# TestBench.net
KiCad netlist of a schematic drawn in EAGLE
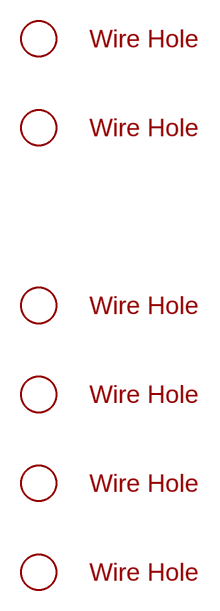
[diagram p0: schematic, sheet 1, part 1 of 2]
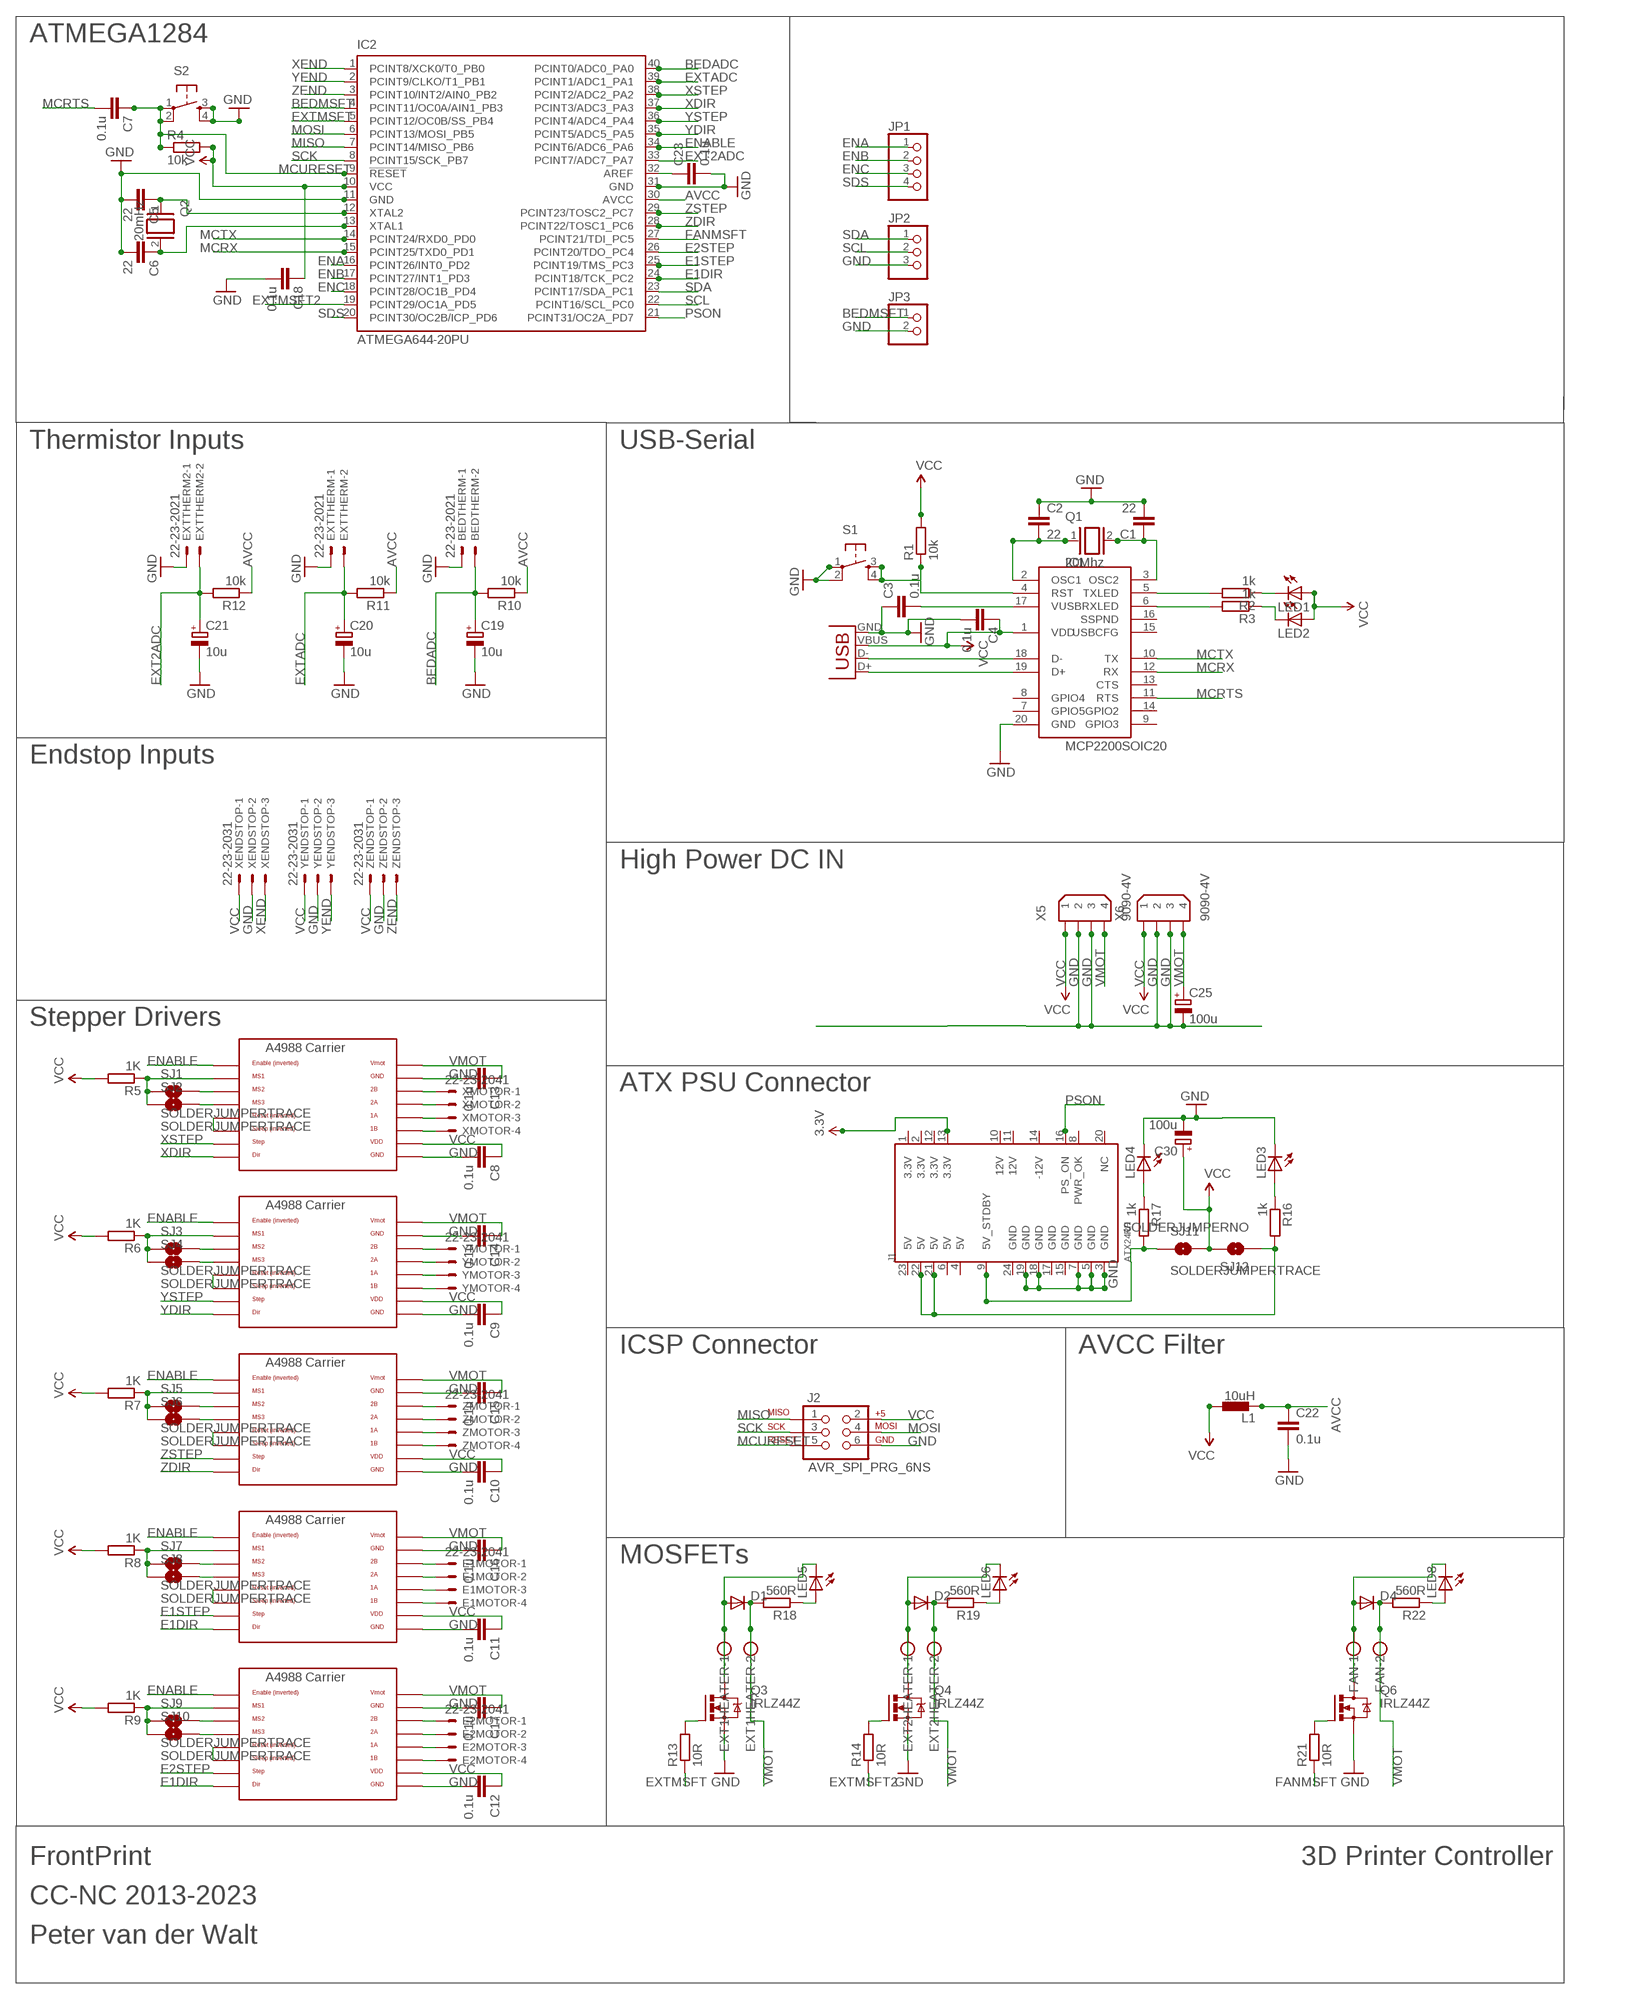
[diagram p1: schematic, sheet 1, part 2 of 2]

(export (version "E")
  (design (tool "Eeschema 10.0.6"))
  (components
    (comp (ref "BEDTHERM")
      (value "22-23-2021")
      (footprint "eagle-import:22-23-2021")
      (fields (field (name "MF") "MOLEX"))
      (libsource (lib "eagle-import") (part "22-23-2021"))
    )
    (comp (ref "C1")
      (value "22")
      (footprint "eagle-import:CAP-PTH-SMALL-KIT")
      (libsource (lib "eagle-import") (part "CAPKIT"))
    )
    (comp (ref "C2")
      (value "22")
      (footprint "eagle-import:CAP-PTH-SMALL-KIT")
      (libsource (lib "eagle-import") (part "CAPKIT"))
    )
    (comp (ref "C3")
      (value "0.1u")
      (footprint "eagle-import:CAP-PTH-SMALL-KIT")
      (libsource (lib "eagle-import") (part "CAPKIT"))
    )
    (comp (ref "C4")
      (value "0.1u")
      (footprint "eagle-import:CAP-PTH-SMALL-KIT")
      (libsource (lib "eagle-import") (part "CAPKIT"))
    )
    (comp (ref "C5")
      (value "22")
      (footprint "eagle-import:CAP-PTH-SMALL-KIT")
      (libsource (lib "eagle-import") (part "CAPKIT"))
    )
    (comp (ref "C6")
      (value "22")
      (footprint "eagle-import:CAP-PTH-SMALL-KIT")
      (libsource (lib "eagle-import") (part "CAPKIT"))
    )
    (comp (ref "C7")
      (value "0.1u")
      (footprint "eagle-import:CAP-PTH-SMALL-KIT")
      (libsource (lib "eagle-import") (part "CAPKIT"))
    )
    (comp (ref "C8")
      (value "0.1u")
      (footprint "eagle-import:CAP-PTH-SMALL-KIT")
      (libsource (lib "eagle-import") (part "CAPKIT"))
    )
    (comp (ref "C9")
      (value "0.1u")
      (footprint "eagle-import:CAP-PTH-SMALL-KIT")
      (libsource (lib "eagle-import") (part "CAPKIT"))
    )
    (comp (ref "C10")
      (value "0.1u")
      (footprint "eagle-import:CAP-PTH-SMALL-KIT")
      (libsource (lib "eagle-import") (part "CAPKIT"))
    )
    (comp (ref "C11")
      (value "0.1u")
      (footprint "eagle-import:CAP-PTH-SMALL-KIT")
      (libsource (lib "eagle-import") (part "CAPKIT"))
    )
    (comp (ref "C12")
      (value "0.1u")
      (footprint "eagle-import:CAP-PTH-SMALL-KIT")
      (libsource (lib "eagle-import") (part "CAPKIT"))
    )
    (comp (ref "C13")
      (value "0.1u")
      (footprint "eagle-import:CAP-PTH-SMALL-KIT")
      (libsource (lib "eagle-import") (part "CAPKIT"))
    )
    (comp (ref "C14")
      (value "0.1u")
      (footprint "eagle-import:CAP-PTH-SMALL-KIT")
      (libsource (lib "eagle-import") (part "CAPKIT"))
    )
    (comp (ref "C15")
      (value "0.1u")
      (footprint "eagle-import:CAP-PTH-SMALL-KIT")
      (libsource (lib "eagle-import") (part "CAPKIT"))
    )
    (comp (ref "C16")
      (value "0.1u")
      (footprint "eagle-import:CAP-PTH-SMALL-KIT")
      (libsource (lib "eagle-import") (part "CAPKIT"))
    )
    (comp (ref "C17")
      (value "0.1u")
      (footprint "eagle-import:CAP-PTH-SMALL-KIT")
      (libsource (lib "eagle-import") (part "CAPKIT"))
    )
    (comp (ref "C18")
      (value "0.1u")
      (footprint "eagle-import:CAP-PTH-SMALL-KIT")
      (libsource (lib "eagle-import") (part "CAPKIT"))
    )
    (comp (ref "C19")
      (value "10u")
      (footprint "eagle-import:E2,5-5")
      (libsource (lib "eagle-import") (part "CPOL-EUE2.5-5"))
    )
    (comp (ref "C20")
      (value "10u")
      (footprint "eagle-import:E2,5-5")
      (libsource (lib "eagle-import") (part "CPOL-EUE2.5-5"))
    )
    (comp (ref "C21")
      (value "10u")
      (footprint "eagle-import:E2,5-5")
      (libsource (lib "eagle-import") (part "CPOL-EUE2.5-5"))
    )
    (comp (ref "C22")
      (value "0.1u")
      (footprint "eagle-import:CAP-PTH-SMALL-KIT")
      (libsource (lib "eagle-import") (part "CAPKIT"))
    )
    (comp (ref "C23")
      (value "0.1u")
      (footprint "eagle-import:CAP-PTH-SMALL-KIT")
      (libsource (lib "eagle-import") (part "CAPKIT"))
    )
    (comp (ref "C25")
      (value "100u")
      (footprint "eagle-import:E5-8,5")
      (libsource (lib "eagle-import") (part "CPOL-EUE5-8.5"))
    )
    (comp (ref "C30")
      (value "100u")
      (footprint "eagle-import:E5-8,5")
      (libsource (lib "eagle-import") (part "CPOL-EUE5-8.5"))
    )
    (comp (ref "D1")
      (value "DIODE1N4148")
      (footprint "eagle-import:DIODE-1N4148")
      (libsource (lib "eagle-import") (part "DIODE1N4148"))
    )
    (comp (ref "D2")
      (value "DIODE1N4148")
      (footprint "eagle-import:DIODE-1N4148")
      (libsource (lib "eagle-import") (part "DIODE1N4148"))
    )
    (comp (ref "D4")
      (value "DIODE1N4148")
      (footprint "eagle-import:DIODE-1N4148")
      (libsource (lib "eagle-import") (part "DIODE1N4148"))
    )
    (comp (ref "E1MOTOR")
      (value "22-23-2041")
      (footprint "eagle-import:22-23-2041")
      (fields (field (name "MF") "MOLEX"))
      (libsource (lib "eagle-import") (part "22-23-2041"))
    )
    (comp (ref "E2MOTOR")
      (value "22-23-2041")
      (footprint "eagle-import:22-23-2041")
      (fields (field (name "MF") "MOLEX"))
      (libsource (lib "eagle-import") (part "22-23-2041"))
    )
    (comp (ref "EPOLOLU")
      (value "POLOLU_A4983CARRIER")
      (footprint "eagle-import:A4988BREAKOUT")
      (libsource (lib "eagle-import") (part "POLOLU_A4983CARRIER"))
    )
    (comp (ref "EPOLOLU2")
      (value "POLOLU_A4983CARRIER")
      (footprint "eagle-import:A4988BREAKOUT")
      (libsource (lib "eagle-import") (part "POLOLU_A4983CARRIER"))
    )
    (comp (ref "EXT1HEATER")
      (value "W237-102")
      (footprint "eagle-import:W237-102")
      (fields (field (name "MPN") "237-102"))
      (libsource (lib "eagle-import") (part "W237-102"))
    )
    (comp (ref "EXT2HEATER")
      (value "W237-102")
      (footprint "eagle-import:W237-102")
      (fields (field (name "MPN") "237-102"))
      (libsource (lib "eagle-import") (part "W237-102"))
    )
    (comp (ref "EXTTHERM")
      (value "22-23-2021")
      (footprint "eagle-import:22-23-2021")
      (fields (field (name "MF") "MOLEX"))
      (libsource (lib "eagle-import") (part "22-23-2021"))
    )
    (comp (ref "EXTTHERM2")
      (value "22-23-2021")
      (footprint "eagle-import:22-23-2021")
      (fields (field (name "MF") "MOLEX"))
      (libsource (lib "eagle-import") (part "22-23-2021"))
    )
    (comp (ref "FAN")
      (value "W237-102")
      (footprint "eagle-import:W237-102")
      (fields (field (name "MPN") "237-102"))
      (libsource (lib "eagle-import") (part "W237-102"))
    )
    (comp (ref "IC1")
      (value "MCP2200SOIC20")
      (footprint "eagle-import:SOIC20")
      (libsource (lib "eagle-import") (part "MCP2200SOIC20"))
    )
    (comp (ref "IC2")
      (value "ATMEGA644-20PU")
      (footprint "eagle-import:DIL40")
      (libsource (lib "eagle-import") (part "ATMEGA644-PU20"))
    )
    (comp (ref "J1")
      (value "ATX24RH")
      (footprint "eagle-import:ATX24_RIGHT_ANGLE")
      (libsource (lib "eagle-import") (part "ATX24RH"))
    )
    (comp (ref "J2")
      (value "AVR_SPI_PRG_6NS")
      (footprint "eagle-import:2X3-NS")
      (libsource (lib "eagle-import") (part "AVR_SPI_PRG_6NS"))
    )
    (comp (ref "JP1")
      (value "PINHD-1X4")
      (footprint "eagle-import:1X04")
      (libsource (lib "eagle-import") (part "PINHD-1X4"))
    )
    (comp (ref "JP2")
      (value "PINHD-1X3")
      (footprint "eagle-import:1X03")
      (libsource (lib "eagle-import") (part "PINHD-1X3"))
    )
    (comp (ref "JP3")
      (value "PINHD-1X2")
      (footprint "eagle-import:1X02")
      (libsource (lib "eagle-import") (part "PINHD-1X2"))
    )
    (comp (ref "L1")
      (value "10uH")
      (footprint "eagle-import:BL01RN1A")
      (libsource (lib "eagle-import") (part "BL01RN1A"))
    )
    (comp (ref "LED1")
      (value "LED3MM")
      (footprint "eagle-import:LED3MM")
      (libsource (lib "eagle-import") (part "LED3MM"))
    )
    (comp (ref "LED2")
      (value "LED3MM")
      (footprint "eagle-import:LED3MM")
      (libsource (lib "eagle-import") (part "LED3MM"))
    )
    (comp (ref "LED3")
      (value "LED3MM")
      (footprint "eagle-import:LED3MM")
      (libsource (lib "eagle-import") (part "LED3MM"))
    )
    (comp (ref "LED4")
      (value "LED3MM")
      (footprint "eagle-import:LED3MM")
      (libsource (lib "eagle-import") (part "LED3MM"))
    )
    (comp (ref "LED5")
      (value "LED3MM")
      (footprint "eagle-import:LED3MM")
      (libsource (lib "eagle-import") (part "LED3MM"))
    )
    (comp (ref "LED6")
      (value "LED3MM")
      (footprint "eagle-import:LED3MM")
      (libsource (lib "eagle-import") (part "LED3MM"))
    )
    (comp (ref "LED8")
      (value "LED3MM")
      (footprint "eagle-import:LED3MM")
      (libsource (lib "eagle-import") (part "LED3MM"))
    )
    (comp (ref "Q1")
      (value "20Mhz")
      (footprint "eagle-import:QS")
      (libsource (lib "eagle-import") (part "XTAL/S"))
    )
    (comp (ref "Q2")
      (value "20mHz")
      (footprint "eagle-import:QS")
      (libsource (lib "eagle-import") (part "XTAL/S"))
    )
    (comp (ref "Q3")
      (value "IRLZ44Z")
      (footprint "eagle-import:TO220BH")
      (libsource (lib "eagle-import") (part "IRLZ44Z"))
    )
    (comp (ref "Q4")
      (value "IRLZ44Z")
      (footprint "eagle-import:TO220BH")
      (libsource (lib "eagle-import") (part "IRLZ44Z"))
    )
    (comp (ref "Q6")
      (value "IRLZ44Z")
      (footprint "eagle-import:TO220BH")
      (libsource (lib "eagle-import") (part "IRLZ44Z"))
    )
    (comp (ref "R1")
      (value "10k")
      (footprint "eagle-import:0204_7")
      (libsource (lib "eagle-import") (part "R-EU_0204/7"))
    )
    (comp (ref "R2")
      (value "1k")
      (footprint "eagle-import:0204_7")
      (libsource (lib "eagle-import") (part "R-EU_0204/7"))
    )
    (comp (ref "R3")
      (value "1k")
      (footprint "eagle-import:0204_7")
      (libsource (lib "eagle-import") (part "R-EU_0204/7"))
    )
    (comp (ref "R4")
      (value "10k")
      (footprint "eagle-import:0204_7")
      (libsource (lib "eagle-import") (part "R-EU_0204/7"))
    )
    (comp (ref "R5")
      (value "1K")
      (footprint "eagle-import:0204_7")
      (libsource (lib "eagle-import") (part "R-EU_0204/7"))
    )
    (comp (ref "R6")
      (value "1K")
      (footprint "eagle-import:0204_7")
      (libsource (lib "eagle-import") (part "R-EU_0204/7"))
    )
    (comp (ref "R7")
      (value "1K")
      (footprint "eagle-import:0204_7")
      (libsource (lib "eagle-import") (part "R-EU_0204/7"))
    )
    (comp (ref "R8")
      (value "1K")
      (footprint "eagle-import:0204_7")
      (libsource (lib "eagle-import") (part "R-EU_0204/7"))
    )
    (comp (ref "R9")
      (value "1K")
      (footprint "eagle-import:0204_7")
      (libsource (lib "eagle-import") (part "R-EU_0204/7"))
    )
    (comp (ref "R10")
      (value "10k")
      (footprint "eagle-import:0204_7")
      (libsource (lib "eagle-import") (part "R-EU_0204/7"))
    )
    (comp (ref "R11")
      (value "10k")
      (footprint "eagle-import:0204_7")
      (libsource (lib "eagle-import") (part "R-EU_0204/7"))
    )
    (comp (ref "R12")
      (value "10k")
      (footprint "eagle-import:0204_7")
      (libsource (lib "eagle-import") (part "R-EU_0204/7"))
    )
    (comp (ref "R13")
      (value "10R")
      (footprint "eagle-import:0204_7")
      (libsource (lib "eagle-import") (part "R-EU_0204/7"))
    )
    (comp (ref "R14")
      (value "10R")
      (footprint "eagle-import:0204_7")
      (libsource (lib "eagle-import") (part "R-EU_0204/7"))
    )
    (comp (ref "R16")
      (value "1k")
      (footprint "eagle-import:0204_7")
      (libsource (lib "eagle-import") (part "R-EU_0204/7"))
    )
    (comp (ref "R17")
      (value "1k")
      (footprint "eagle-import:0204_7")
      (libsource (lib "eagle-import") (part "R-EU_0204/7"))
    )
    (comp (ref "R18")
      (value "560R")
      (footprint "eagle-import:0204_7")
      (libsource (lib "eagle-import") (part "R-EU_0204/7"))
    )
    (comp (ref "R19")
      (value "560R")
      (footprint "eagle-import:0204_7")
      (libsource (lib "eagle-import") (part "R-EU_0204/7"))
    )
    (comp (ref "R21")
      (value "10R")
      (footprint "eagle-import:0204_7")
      (libsource (lib "eagle-import") (part "R-EU_0204/7"))
    )
    (comp (ref "R22")
      (value "560R")
      (footprint "eagle-import:0204_7")
      (libsource (lib "eagle-import") (part "R-EU_0204/7"))
    )
    (comp (ref "S1")
      (value "TAC_SWITCHPTH")
      (footprint "eagle-import:TACTILE-PTH")
      (libsource (lib "eagle-import") (part "TAC_SWITCHPTH"))
    )
    (comp (ref "S2")
      (value "TAC_SWITCHPTH")
      (footprint "eagle-import:TACTILE-PTH")
      (libsource (lib "eagle-import") (part "TAC_SWITCHPTH"))
    )
    (comp (ref "SJ1")
      (value "SOLDERJUMPERTRACE")
      (footprint "eagle-import:SJ_2S-TRACE")
      (libsource (lib "eagle-import") (part "SOLDERJUMPERTRACE"))
    )
    (comp (ref "SJ2")
      (value "SOLDERJUMPERTRACE")
      (footprint "eagle-import:SJ_2S-TRACE")
      (libsource (lib "eagle-import") (part "SOLDERJUMPERTRACE"))
    )
    (comp (ref "SJ3")
      (value "SOLDERJUMPERTRACE")
      (footprint "eagle-import:SJ_2S-TRACE")
      (libsource (lib "eagle-import") (part "SOLDERJUMPERTRACE"))
    )
    (comp (ref "SJ4")
      (value "SOLDERJUMPERTRACE")
      (footprint "eagle-import:SJ_2S-TRACE")
      (libsource (lib "eagle-import") (part "SOLDERJUMPERTRACE"))
    )
    (comp (ref "SJ5")
      (value "SOLDERJUMPERTRACE")
      (footprint "eagle-import:SJ_2S-TRACE")
      (libsource (lib "eagle-import") (part "SOLDERJUMPERTRACE"))
    )
    (comp (ref "SJ6")
      (value "SOLDERJUMPERTRACE")
      (footprint "eagle-import:SJ_2S-TRACE")
      (libsource (lib "eagle-import") (part "SOLDERJUMPERTRACE"))
    )
    (comp (ref "SJ7")
      (value "SOLDERJUMPERTRACE")
      (footprint "eagle-import:SJ_2S-TRACE")
      (libsource (lib "eagle-import") (part "SOLDERJUMPERTRACE"))
    )
    (comp (ref "SJ8")
      (value "SOLDERJUMPERTRACE")
      (footprint "eagle-import:SJ_2S-TRACE")
      (libsource (lib "eagle-import") (part "SOLDERJUMPERTRACE"))
    )
    (comp (ref "SJ9")
      (value "SOLDERJUMPERTRACE")
      (footprint "eagle-import:SJ_2S-TRACE")
      (libsource (lib "eagle-import") (part "SOLDERJUMPERTRACE"))
    )
    (comp (ref "SJ10")
      (value "SOLDERJUMPERTRACE")
      (footprint "eagle-import:SJ_2S-TRACE")
      (libsource (lib "eagle-import") (part "SOLDERJUMPERTRACE"))
    )
    (comp (ref "SJ11")
      (value "SOLDERJUMPERTRACE")
      (footprint "eagle-import:SJ_2S-TRACE")
      (libsource (lib "eagle-import") (part "SOLDERJUMPERTRACE"))
    )
    (comp (ref "SJ12")
      (value "SOLDERJUMPERNO")
      (footprint "eagle-import:SJ_2S-NO")
      (libsource (lib "eagle-import") (part "SOLDERJUMPERNO"))
    )
    (comp (ref "U$1")
      (value "3MMHOLE")
      (footprint "eagle-import:3MMHOLE")
      (libsource (lib "eagle-import") (part "3MMHOLE"))
    )
    (comp (ref "U$3")
      (value "3MMHOLE")
      (footprint "eagle-import:3MMHOLE")
      (libsource (lib "eagle-import") (part "3MMHOLE"))
    )
    (comp (ref "U$5")
      (value "3MMHOLE")
      (footprint "eagle-import:3MMHOLE")
      (libsource (lib "eagle-import") (part "3MMHOLE"))
    )
    (comp (ref "U$6")
      (value "3MMHOLE")
      (footprint "eagle-import:3MMHOLE")
      (libsource (lib "eagle-import") (part "3MMHOLE"))
    )
    (comp (ref "U$7")
      (value "3MMHOLE")
      (footprint "eagle-import:3MMHOLE")
      (libsource (lib "eagle-import") (part "3MMHOLE"))
    )
    (comp (ref "U$8")
      (value "3MMHOLE")
      (footprint "eagle-import:3MMHOLE")
      (libsource (lib "eagle-import") (part "3MMHOLE"))
    )
    (comp (ref "X1")
      (value "USBPTH")
      (footprint "eagle-import:USB-B-PTH")
      (libsource (lib "eagle-import") (part "USBPTH"))
    )
    (comp (ref "X5")
      (value "9090-4V")
      (footprint "eagle-import:9090-4V")
      (libsource (lib "eagle-import") (part "9090-4V"))
    )
    (comp (ref "X6")
      (value "9090-4V")
      (footprint "eagle-import:9090-4V")
      (libsource (lib "eagle-import") (part "9090-4V"))
    )
    (comp (ref "XENDSTOP")
      (value "22-23-2031")
      (footprint "eagle-import:22-23-2031")
      (fields (field (name "MF") "MOLEX"))
      (libsource (lib "eagle-import") (part "22-23-2031"))
    )
    (comp (ref "XMOTOR")
      (value "22-23-2041")
      (footprint "eagle-import:22-23-2041")
      (fields (field (name "MF") "MOLEX"))
      (libsource (lib "eagle-import") (part "22-23-2041"))
    )
    (comp (ref "XPOLOLU")
      (value "POLOLU_A4983CARRIER")
      (footprint "eagle-import:A4988BREAKOUT")
      (libsource (lib "eagle-import") (part "POLOLU_A4983CARRIER"))
    )
    (comp (ref "YENDSTOP")
      (value "22-23-2031")
      (footprint "eagle-import:22-23-2031")
      (fields (field (name "MF") "MOLEX"))
      (libsource (lib "eagle-import") (part "22-23-2031"))
    )
    (comp (ref "YMOTOR")
      (value "22-23-2041")
      (footprint "eagle-import:22-23-2041")
      (fields (field (name "MF") "MOLEX"))
      (libsource (lib "eagle-import") (part "22-23-2041"))
    )
    (comp (ref "YPOLOLU")
      (value "POLOLU_A4983CARRIER")
      (footprint "eagle-import:A4988BREAKOUT")
      (libsource (lib "eagle-import") (part "POLOLU_A4983CARRIER"))
    )
    (comp (ref "ZENDSTOP")
      (value "22-23-2031")
      (footprint "eagle-import:22-23-2031")
      (fields (field (name "MF") "MOLEX"))
      (libsource (lib "eagle-import") (part "22-23-2031"))
    )
    (comp (ref "ZMOTOR")
      (value "22-23-2041")
      (footprint "eagle-import:22-23-2041")
      (fields (field (name "MF") "MOLEX"))
      (libsource (lib "eagle-import") (part "22-23-2041"))
    )
    (comp (ref "ZPOLOLU")
      (value "POLOLU_A4983CARRIER")
      (footprint "eagle-import:A4988BREAKOUT")
      (libsource (lib "eagle-import") (part "POLOLU_A4983CARRIER"))
    )
  )
  (nets
    (net (code "1") (name "/AVCC") (class "Default")
      (node (ref "C22") (pin "1") (pinfunction "1_1") (pintype "passive"))
      (node (ref "IC2") (pin "30") (pinfunction "AVCC_30") (pintype "power_in"))
      (node (ref "L1") (pin "1") (pinfunction "1_1") (pintype "passive"))
      (node (ref "R10") (pin "1") (pinfunction "1_1") (pintype "passive"))
      (node (ref "R11") (pin "1") (pinfunction "1_1") (pintype "passive"))
      (node (ref "R12") (pin "1") (pinfunction "1_1") (pintype "passive"))
    )
    (net (code "2") (name "/BEDADC") (class "Default")
      (node (ref "BEDTHERM") (pin "2") (pinfunction "S_2") (pintype "passive"))
      (node (ref "C19") (pin "+") (pinfunction "+_+") (pintype "passive"))
      (node (ref "IC2") (pin "40") (pinfunction "PCINT0/ADC0_PA0_40") (pintype "bidirectional"))
      (node (ref "R10") (pin "2") (pinfunction "2_2") (pintype "passive"))
    )
    (net (code "3") (name "/BEDMSFT") (class "Default")
      (node (ref "IC2") (pin "4") (pinfunction "PCINT11/OC0A/AIN1_PB3_4") (pintype "bidirectional"))
      (node (ref "JP3") (pin "1") (pinfunction "1_1") (pintype "passive"))
    )
    (net (code "4") (name "/E1DIR") (class "Default")
      (node (ref "EPOLOLU") (pin "DIR") (pinfunction "DIR_DIR") (pintype "input"))
      (node (ref "EPOLOLU2") (pin "DIR") (pinfunction "DIR_DIR") (pintype "input"))
      (node (ref "IC2") (pin "24") (pinfunction "PCINT18/TCK_PC2_24") (pintype "bidirectional"))
    )
    (net (code "5") (name "/E1STEP") (class "Default")
      (node (ref "EPOLOLU") (pin "STEP") (pinfunction "STEP_STEP") (pintype "input"))
      (node (ref "IC2") (pin "25") (pinfunction "PCINT19/TMS_PC3_25") (pintype "bidirectional"))
    )
    (net (code "6") (name "/E2STEP") (class "Default")
      (node (ref "EPOLOLU2") (pin "STEP") (pinfunction "STEP_STEP") (pintype "input"))
      (node (ref "IC2") (pin "26") (pinfunction "PCINT20/TDO_PC4_26") (pintype "bidirectional"))
    )
    (net (code "7") (name "/ENA") (class "Default")
      (node (ref "IC2") (pin "16") (pinfunction "PCINT26/INT0_PD2_16") (pintype "bidirectional"))
      (node (ref "JP1") (pin "1") (pinfunction "1_1") (pintype "passive"))
    )
    (net (code "8") (name "/ENABLE") (class "Default")
      (node (ref "EPOLOLU") (pin "EN") (pinfunction "EN_EN") (pintype "input"))
      (node (ref "EPOLOLU2") (pin "EN") (pinfunction "EN_EN") (pintype "input"))
      (node (ref "IC2") (pin "34") (pinfunction "PCINT6/ADC6_PA6_34") (pintype "bidirectional"))
      (node (ref "XPOLOLU") (pin "EN") (pinfunction "EN_EN") (pintype "input"))
      (node (ref "YPOLOLU") (pin "EN") (pinfunction "EN_EN") (pintype "input"))
      (node (ref "ZPOLOLU") (pin "EN") (pinfunction "EN_EN") (pintype "input"))
    )
    (net (code "9") (name "/ENB") (class "Default")
      (node (ref "IC2") (pin "17") (pinfunction "PCINT27/INT1_PD3_17") (pintype "bidirectional"))
      (node (ref "JP1") (pin "2") (pinfunction "2_2") (pintype "passive"))
    )
    (net (code "10") (name "/ENC") (class "Default")
      (node (ref "IC2") (pin "18") (pinfunction "PCINT28/OC1B_PD4_18") (pintype "bidirectional"))
      (node (ref "JP1") (pin "3") (pinfunction "3_3") (pintype "passive"))
    )
    (net (code "11") (name "/EXT2ADC") (class "Default")
      (node (ref "C21") (pin "+") (pinfunction "+_+") (pintype "passive"))
      (node (ref "EXTTHERM2") (pin "2") (pinfunction "S_2") (pintype "passive"))
      (node (ref "IC2") (pin "33") (pinfunction "PCINT7/ADC7_PA7_33") (pintype "bidirectional"))
      (node (ref "R12") (pin "2") (pinfunction "2_2") (pintype "passive"))
    )
    (net (code "12") (name "/EXTADC") (class "Default")
      (node (ref "C20") (pin "+") (pinfunction "+_+") (pintype "passive"))
      (node (ref "EXTTHERM") (pin "2") (pinfunction "S_2") (pintype "passive"))
      (node (ref "IC2") (pin "39") (pinfunction "PCINT1/ADC1_PA1_39") (pintype "bidirectional"))
      (node (ref "R11") (pin "2") (pinfunction "2_2") (pintype "passive"))
    )
    (net (code "13") (name "/EXTMSFT") (class "Default")
      (node (ref "IC2") (pin "5") (pinfunction "PCINT12/OC0B/SS_PB4_5") (pintype "bidirectional"))
      (node (ref "R13") (pin "1") (pinfunction "1_1") (pintype "passive"))
    )
    (net (code "14") (name "/EXTMSFT2") (class "Default")
      (node (ref "IC2") (pin "19") (pinfunction "PCINT29/OC1A_PD5_19") (pintype "bidirectional"))
      (node (ref "R14") (pin "1") (pinfunction "1_1") (pintype "passive"))
    )
    (net (code "15") (name "/FANMSFT") (class "Default")
      (node (ref "IC2") (pin "27") (pinfunction "PCINT21/TDI_PC5_27") (pintype "bidirectional"))
      (node (ref "R21") (pin "1") (pinfunction "1_1") (pintype "passive"))
    )
    (net (code "16") (name "/MCRTS") (class "Default")
      (node (ref "C7") (pin "2") (pinfunction "2_2") (pintype "passive"))
      (node (ref "IC1") (pin "11") (pinfunction "RTS_11") (pintype "bidirectional"))
    )
    (net (code "17") (name "/MCRX") (class "Default")
      (node (ref "IC1") (pin "12") (pinfunction "RX_12") (pintype "bidirectional"))
      (node (ref "IC2") (pin "15") (pinfunction "PCINT25/TXD0_PD1_15") (pintype "bidirectional"))
    )
    (net (code "18") (name "/MCTX") (class "Default")
      (node (ref "IC1") (pin "10") (pinfunction "TX_10") (pintype "bidirectional"))
      (node (ref "IC2") (pin "14") (pinfunction "PCINT24/RXD0_PD0_14") (pintype "bidirectional"))
    )
    (net (code "19") (name "/MCURESET") (class "Default")
      (node (ref "C7") (pin "1") (pinfunction "1_1") (pintype "passive"))
      (node (ref "IC2") (pin "9") (pinfunction "~{RESET}_9") (pintype "input"))
      (node (ref "J2") (pin "5") (pinfunction "5_5") (pintype "passive"))
      (node (ref "R4") (pin "1") (pinfunction "1_1") (pintype "passive"))
      (node (ref "S2") (pin "1") (pinfunction "1_1") (pintype "passive"))
      (node (ref "S2") (pin "2") (pinfunction "2_2") (pintype "passive"))
    )
    (net (code "20") (name "/MISO") (class "Default")
      (node (ref "IC2") (pin "7") (pinfunction "PCINT14/MISO_PB6_7") (pintype "bidirectional"))
      (node (ref "J2") (pin "1") (pinfunction "1_1") (pintype "passive"))
    )
    (net (code "21") (name "/MOSI") (class "Default")
      (node (ref "IC2") (pin "6") (pinfunction "PCINT13/MOSI_PB5_6") (pintype "bidirectional"))
      (node (ref "J2") (pin "4") (pinfunction "4_4") (pintype "passive"))
    )
    (net (code "22") (name "/PSON") (class "Default")
      (node (ref "IC2") (pin "21") (pinfunction "PCINT31/OC2A_PD7_21") (pintype "bidirectional"))
      (node (ref "J1") (pin "16") (pinfunction "PS_ON_16") (pintype "bidirectional"))
    )
    (net (code "23") (name "/SCK") (class "Default")
      (node (ref "IC2") (pin "8") (pinfunction "PCINT15/SCK_PB7_8") (pintype "bidirectional"))
      (node (ref "J2") (pin "3") (pinfunction "3_3") (pintype "passive"))
    )
    (net (code "24") (name "/SCL") (class "Default")
      (node (ref "IC2") (pin "22") (pinfunction "PCINT16/SCL_PC0_22") (pintype "bidirectional"))
      (node (ref "JP2") (pin "2") (pinfunction "2_2") (pintype "passive"))
    )
    (net (code "25") (name "/SDA") (class "Default")
      (node (ref "IC2") (pin "23") (pinfunction "PCINT17/SDA_PC1_23") (pintype "bidirectional"))
      (node (ref "JP2") (pin "1") (pinfunction "1_1") (pintype "passive"))
    )
    (net (code "26") (name "/SDS") (class "Default")
      (node (ref "IC2") (pin "20") (pinfunction "PCINT30/OC2B/ICP_PD6_20") (pintype "bidirectional"))
      (node (ref "JP1") (pin "4") (pinfunction "4_4") (pintype "passive"))
    )
    (net (code "27") (name "/VMOT") (class "Default")
      (node (ref "C13") (pin "1") (pinfunction "1_1") (pintype "passive"))
      (node (ref "C14") (pin "1") (pinfunction "1_1") (pintype "passive"))
      (node (ref "C15") (pin "1") (pinfunction "1_1") (pintype "passive"))
      (node (ref "C16") (pin "1") (pinfunction "1_1") (pintype "passive"))
      (node (ref "C17") (pin "1") (pinfunction "1_1") (pintype "passive"))
      (node (ref "C25") (pin "+") (pinfunction "+_+") (pintype "passive"))
      (node (ref "D1") (pin "C") (pinfunction "C_C") (pintype "passive"))
      (node (ref "D2") (pin "C") (pinfunction "C_C") (pintype "passive"))
      (node (ref "D4") (pin "C") (pinfunction "C_C") (pintype "passive"))
      (node (ref "EPOLOLU") (pin "VMOT") (pinfunction "VMOT_VMOT") (pintype "power_in"))
      (node (ref "EPOLOLU2") (pin "VMOT") (pinfunction "VMOT_VMOT") (pintype "power_in"))
      (node (ref "EXT1HEATER") (pin "2") (pinfunction "KL_2") (pintype "passive"))
      (node (ref "EXT2HEATER") (pin "2") (pinfunction "KL_2") (pintype "passive"))
      (node (ref "FAN") (pin "2") (pinfunction "KL_2") (pintype "passive"))
      (node (ref "R18") (pin "2") (pinfunction "2_2") (pintype "passive"))
      (node (ref "R19") (pin "2") (pinfunction "2_2") (pintype "passive"))
      (node (ref "R22") (pin "2") (pinfunction "2_2") (pintype "passive"))
      (node (ref "X5") (pin "4") (pinfunction "4_4") (pintype "passive"))
      (node (ref "X6") (pin "4") (pinfunction "4_4") (pintype "passive"))
      (node (ref "XPOLOLU") (pin "VMOT") (pinfunction "VMOT_VMOT") (pintype "power_in"))
      (node (ref "YPOLOLU") (pin "VMOT") (pinfunction "VMOT_VMOT") (pintype "power_in"))
      (node (ref "ZPOLOLU") (pin "VMOT") (pinfunction "VMOT_VMOT") (pintype "power_in"))
    )
    (net (code "28") (name "/XDIR") (class "Default")
      (node (ref "IC2") (pin "37") (pinfunction "PCINT3/ADC3_PA3_37") (pintype "bidirectional"))
      (node (ref "XPOLOLU") (pin "DIR") (pinfunction "DIR_DIR") (pintype "input"))
    )
    (net (code "29") (name "/XEND") (class "Default")
      (node (ref "IC2") (pin "1") (pinfunction "PCINT8/XCK0/T0_PB0_1") (pintype "bidirectional"))
      (node (ref "XENDSTOP") (pin "3") (pinfunction "S_3") (pintype "passive"))
    )
    (net (code "30") (name "/XSTEP") (class "Default")
      (node (ref "IC2") (pin "38") (pinfunction "PCINT2/ADC2_PA2_38") (pintype "bidirectional"))
      (node (ref "XPOLOLU") (pin "STEP") (pinfunction "STEP_STEP") (pintype "input"))
    )
    (net (code "31") (name "/YDIR") (class "Default")
      (node (ref "IC2") (pin "35") (pinfunction "PCINT5/ADC5_PA5_35") (pintype "bidirectional"))
      (node (ref "YPOLOLU") (pin "DIR") (pinfunction "DIR_DIR") (pintype "input"))
    )
    (net (code "32") (name "/YEND") (class "Default")
      (node (ref "IC2") (pin "2") (pinfunction "PCINT9/CLKO/T1_PB1_2") (pintype "bidirectional"))
      (node (ref "YENDSTOP") (pin "3") (pinfunction "S_3") (pintype "passive"))
    )
    (net (code "33") (name "/YSTEP") (class "Default")
      (node (ref "IC2") (pin "36") (pinfunction "PCINT4/ADC4_PA4_36") (pintype "bidirectional"))
      (node (ref "YPOLOLU") (pin "STEP") (pinfunction "STEP_STEP") (pintype "input"))
    )
    (net (code "34") (name "/ZDIR") (class "Default")
      (node (ref "IC2") (pin "28") (pinfunction "PCINT22/TOSC1_PC6_28") (pintype "bidirectional"))
      (node (ref "ZPOLOLU") (pin "DIR") (pinfunction "DIR_DIR") (pintype "input"))
    )
    (net (code "35") (name "/ZEND") (class "Default")
      (node (ref "IC2") (pin "3") (pinfunction "PCINT10/INT2/AIN0_PB2_3") (pintype "bidirectional"))
      (node (ref "ZENDSTOP") (pin "3") (pinfunction "S_3") (pintype "passive"))
    )
    (net (code "36") (name "/ZSTEP") (class "Default")
      (node (ref "IC2") (pin "29") (pinfunction "PCINT23/TOSC2_PC7_29") (pintype "bidirectional"))
      (node (ref "ZPOLOLU") (pin "STEP") (pinfunction "STEP_STEP") (pintype "input"))
    )
    (net (code "37") (name "3.3V") (class "Default")
      (node (ref "J1") (pin "13") (pinfunction "3.3V_13") (pintype "bidirectional"))
    )
    (net (code "38") (name "GND") (class "Default")
      (node (ref "BEDTHERM") (pin "1") (pinfunction "S_1") (pintype "passive"))
      (node (ref "C1") (pin "2") (pinfunction "2_2") (pintype "passive"))
      (node (ref "C10") (pin "2") (pinfunction "2_2") (pintype "passive"))
      (node (ref "C11") (pin "2") (pinfunction "2_2") (pintype "passive"))
      (node (ref "C12") (pin "2") (pinfunction "2_2") (pintype "passive"))
      (node (ref "C13") (pin "2") (pinfunction "2_2") (pintype "passive"))
      (node (ref "C14") (pin "2") (pinfunction "2_2") (pintype "passive"))
      (node (ref "C15") (pin "2") (pinfunction "2_2") (pintype "passive"))
      (node (ref "C16") (pin "2") (pinfunction "2_2") (pintype "passive"))
      (node (ref "C17") (pin "2") (pinfunction "2_2") (pintype "passive"))
      (node (ref "C18") (pin "2") (pinfunction "2_2") (pintype "passive"))
      (node (ref "C19") (pin "-") (pinfunction "-_-") (pintype "passive"))
      (node (ref "C2") (pin "1") (pinfunction "1_1") (pintype "passive"))
      (node (ref "C20") (pin "-") (pinfunction "-_-") (pintype "passive"))
      (node (ref "C21") (pin "-") (pinfunction "-_-") (pintype "passive"))
      (node (ref "C22") (pin "2") (pinfunction "2_2") (pintype "passive"))
      (node (ref "C23") (pin "2") (pinfunction "2_2") (pintype "passive"))
      (node (ref "C25") (pin "-") (pinfunction "-_-") (pintype "passive"))
      (node (ref "C3") (pin "1") (pinfunction "1_1") (pintype "passive"))
      (node (ref "C30") (pin "-") (pinfunction "-_-") (pintype "passive"))
      (node (ref "C4") (pin "2") (pinfunction "2_2") (pintype "passive"))
      (node (ref "C5") (pin "2") (pinfunction "2_2") (pintype "passive"))
      (node (ref "C6") (pin "2") (pinfunction "2_2") (pintype "passive"))
      (node (ref "C8") (pin "2") (pinfunction "2_2") (pintype "passive"))
      (node (ref "C9") (pin "2") (pinfunction "2_2") (pintype "passive"))
      (node (ref "EPOLOLU") (pin "GND") (pinfunction "GND_GND") (pintype "power_in"))
      (node (ref "EPOLOLU") (pin "GND@0") (pinfunction "GND_GND@0") (pintype "power_in"))
      (node (ref "EPOLOLU2") (pin "GND") (pinfunction "GND_GND") (pintype "power_in"))
      (node (ref "EPOLOLU2") (pin "GND@0") (pinfunction "GND_GND@0") (pintype "power_in"))
      (node (ref "EXTTHERM") (pin "1") (pinfunction "S_1") (pintype "passive"))
      (node (ref "EXTTHERM2") (pin "1") (pinfunction "S_1") (pintype "passive"))
      (node (ref "IC1") (pin "20") (pinfunction "GND_20") (pintype "bidirectional"))
      (node (ref "IC2") (pin "11") (pinfunction "GND_11") (pintype "power_in"))
      (node (ref "IC2") (pin "31") (pinfunction "GND_31") (pintype "power_in"))
      (node (ref "J1") (pin "18") (pinfunction "GND_18") (pintype "bidirectional"))
      (node (ref "J1") (pin "19") (pinfunction "GND_19") (pintype "bidirectional"))
      (node (ref "J1") (pin "3") (pinfunction "GND_3") (pintype "bidirectional"))
      (node (ref "J1") (pin "5") (pinfunction "GND_5") (pintype "bidirectional"))
      (node (ref "J1") (pin "7") (pinfunction "GND_7") (pintype "bidirectional"))
      (node (ref "J2") (pin "6") (pinfunction "6_6") (pintype "passive"))
      (node (ref "JP2") (pin "3") (pinfunction "3_3") (pintype "passive"))
      (node (ref "JP3") (pin "2") (pinfunction "2_2") (pintype "passive"))
      (node (ref "LED3") (pin "K") (pinfunction "C_K") (pintype "passive"))
      (node (ref "LED4") (pin "K") (pinfunction "C_K") (pintype "passive"))
      (node (ref "Q3") (pin "S") (pinfunction "S_S") (pintype "passive"))
      (node (ref "Q4") (pin "S") (pinfunction "S_S") (pintype "passive"))
      (node (ref "Q6") (pin "S") (pinfunction "S_S") (pintype "passive"))
      (node (ref "S1") (pin "1") (pinfunction "1_1") (pintype "passive"))
      (node (ref "S1") (pin "2") (pinfunction "2_2") (pintype "passive"))
      (node (ref "S2") (pin "3") (pinfunction "3_3") (pintype "passive"))
      (node (ref "S2") (pin "4") (pinfunction "4_4") (pintype "passive"))
      (node (ref "X1") (pin "GND") (pinfunction "GND_GND") (pintype "bidirectional"))
      (node (ref "X5") (pin "2") (pinfunction "2_2") (pintype "passive"))
      (node (ref "X5") (pin "3") (pinfunction "3_3") (pintype "passive"))
      (node (ref "X6") (pin "2") (pinfunction "2_2") (pintype "passive"))
      (node (ref "X6") (pin "3") (pinfunction "3_3") (pintype "passive"))
      (node (ref "XENDSTOP") (pin "2") (pinfunction "S_2") (pintype "passive"))
      (node (ref "XPOLOLU") (pin "GND") (pinfunction "GND_GND") (pintype "power_in"))
      (node (ref "XPOLOLU") (pin "GND@0") (pinfunction "GND_GND@0") (pintype "power_in"))
      (node (ref "YENDSTOP") (pin "2") (pinfunction "S_2") (pintype "passive"))
      (node (ref "YPOLOLU") (pin "GND") (pinfunction "GND_GND") (pintype "power_in"))
      (node (ref "YPOLOLU") (pin "GND@0") (pinfunction "GND_GND@0") (pintype "power_in"))
      (node (ref "ZENDSTOP") (pin "2") (pinfunction "S_2") (pintype "passive"))
      (node (ref "ZPOLOLU") (pin "GND") (pinfunction "GND_GND") (pintype "power_in"))
      (node (ref "ZPOLOLU") (pin "GND@0") (pinfunction "GND_GND@0") (pintype "power_in"))
    )
    (net (code "39") (name "Net-(E1MOTORA-S)") (class "Default")
      (node (ref "E1MOTOR") (pin "1") (pinfunction "S_1") (pintype "passive"))
      (node (ref "EPOLOLU") (pin "2B") (pinfunction "2B_2B") (pintype "output"))
    )
    (net (code "40") (name "Net-(E1MOTORB-S)") (class "Default")
      (node (ref "E1MOTOR") (pin "2") (pinfunction "S_2") (pintype "passive"))
      (node (ref "EPOLOLU") (pin "2A") (pinfunction "2A_2A") (pintype "output"))
    )
    (net (code "41") (name "Net-(E1MOTORC-S)") (class "Default")
      (node (ref "E1MOTOR") (pin "3") (pinfunction "S_3") (pintype "passive"))
      (node (ref "EPOLOLU") (pin "1A") (pinfunction "1A_1A") (pintype "output"))
    )
    (net (code "42") (name "Net-(E1MOTORD-S)") (class "Default")
      (node (ref "E1MOTOR") (pin "4") (pinfunction "S_4") (pintype "passive"))
      (node (ref "EPOLOLU") (pin "1B") (pinfunction "1B_1B") (pintype "output"))
    )
    (net (code "43") (name "Net-(E2MOTORA-S)") (class "Default")
      (node (ref "E2MOTOR") (pin "1") (pinfunction "S_1") (pintype "passive"))
      (node (ref "EPOLOLU2") (pin "2B") (pinfunction "2B_2B") (pintype "output"))
    )
    (net (code "44") (name "Net-(E2MOTORB-S)") (class "Default")
      (node (ref "E2MOTOR") (pin "2") (pinfunction "S_2") (pintype "passive"))
      (node (ref "EPOLOLU2") (pin "2A") (pinfunction "2A_2A") (pintype "output"))
    )
    (net (code "45") (name "Net-(E2MOTORC-S)") (class "Default")
      (node (ref "E2MOTOR") (pin "3") (pinfunction "S_3") (pintype "passive"))
      (node (ref "EPOLOLU2") (pin "1A") (pinfunction "1A_1A") (pintype "output"))
    )
    (net (code "46") (name "Net-(E2MOTORD-S)") (class "Default")
      (node (ref "E2MOTOR") (pin "4") (pinfunction "S_4") (pintype "passive"))
      (node (ref "EPOLOLU2") (pin "1B") (pinfunction "1B_1B") (pintype "output"))
    )
    (net (code "47") (name "Net-(EPOLOLU-PadMS1)") (class "Default")
      (node (ref "EPOLOLU") (pin "MS1") (pinfunction "MS1_MS1") (pintype "input"))
      (node (ref "R8") (pin "1") (pinfunction "1_1") (pintype "passive"))
      (node (ref "SJ7") (pin "1") (pinfunction "1_1") (pintype "passive"))
      (node (ref "SJ8") (pin "1") (pinfunction "1_1") (pintype "passive"))
    )
    (net (code "48") (name "Net-(EPOLOLU-PadMS2)") (class "Default")
      (node (ref "EPOLOLU") (pin "MS2") (pinfunction "MS2_MS2") (pintype "input"))
      (node (ref "SJ7") (pin "2") (pinfunction "2_2") (pintype "passive"))
    )
    (net (code "49") (name "Net-(EPOLOLU-PadMS3)") (class "Default")
      (node (ref "EPOLOLU") (pin "MS3") (pinfunction "MS3_MS3") (pintype "input"))
      (node (ref "SJ8") (pin "2") (pinfunction "2_2") (pintype "passive"))
    )
    (net (code "50") (name "Net-(EPOLOLU-SLEEP)") (class "Default")
      (node (ref "EPOLOLU") (pin "RST") (pinfunction "RST_RST") (pintype "input"))
      (node (ref "EPOLOLU") (pin "SLP") (pinfunction "SLEEP_SLP") (pintype "input"))
    )
    (net (code "51") (name "Net-(EPOLOLU2-PadMS1)") (class "Default")
      (node (ref "EPOLOLU2") (pin "MS1") (pinfunction "MS1_MS1") (pintype "input"))
      (node (ref "R9") (pin "1") (pinfunction "1_1") (pintype "passive"))
      (node (ref "SJ10") (pin "1") (pinfunction "1_1") (pintype "passive"))
      (node (ref "SJ9") (pin "1") (pinfunction "1_1") (pintype "passive"))
    )
    (net (code "52") (name "Net-(EPOLOLU2-PadMS2)") (class "Default")
      (node (ref "EPOLOLU2") (pin "MS2") (pinfunction "MS2_MS2") (pintype "input"))
      (node (ref "SJ9") (pin "2") (pinfunction "2_2") (pintype "passive"))
    )
    (net (code "53") (name "Net-(EPOLOLU2-PadMS3)") (class "Default")
      (node (ref "EPOLOLU2") (pin "MS3") (pinfunction "MS3_MS3") (pintype "input"))
      (node (ref "SJ10") (pin "2") (pinfunction "2_2") (pintype "passive"))
    )
    (net (code "54") (name "Net-(EPOLOLU2-SLEEP)") (class "Default")
      (node (ref "EPOLOLU2") (pin "RST") (pinfunction "RST_RST") (pintype "input"))
      (node (ref "EPOLOLU2") (pin "SLP") (pinfunction "SLEEP_SLP") (pintype "input"))
    )
    (net (code "55") (name "Net-(EXT1HEATERA-KL)") (class "Default")
      (node (ref "D1") (pin "A") (pinfunction "A_A") (pintype "passive"))
      (node (ref "EXT1HEATER") (pin "1") (pinfunction "KL_1") (pintype "passive"))
      (node (ref "LED5") (pin "K") (pinfunction "C_K") (pintype "passive"))
      (node (ref "Q3") (pin "D") (pinfunction "D_D") (pintype "passive"))
    )
    (net (code "56") (name "Net-(EXT2HEATERA-KL)") (class "Default")
      (node (ref "D2") (pin "A") (pinfunction "A_A") (pintype "passive"))
      (node (ref "EXT2HEATER") (pin "1") (pinfunction "KL_1") (pintype "passive"))
      (node (ref "LED6") (pin "K") (pinfunction "C_K") (pintype "passive"))
      (node (ref "Q4") (pin "D") (pinfunction "D_D") (pintype "passive"))
    )
    (net (code "57") (name "Net-(FANA-KL)") (class "Default")
      (node (ref "D4") (pin "A") (pinfunction "A_A") (pintype "passive"))
      (node (ref "FAN") (pin "1") (pinfunction "KL_1") (pintype "passive"))
      (node (ref "LED8") (pin "K") (pinfunction "C_K") (pintype "passive"))
      (node (ref "Q6") (pin "D") (pinfunction "D_D") (pintype "passive"))
    )
    (net (code "58") (name "Net-(IC1-D+)") (class "Default")
      (node (ref "IC1") (pin "19") (pinfunction "D+_19") (pintype "bidirectional"))
      (node (ref "X1") (pin "D+") (pinfunction "D+_D+") (pintype "bidirectional"))
    )
    (net (code "59") (name "Net-(IC1-D-)") (class "Default")
      (node (ref "IC1") (pin "18") (pinfunction "D-_18") (pintype "bidirectional"))
      (node (ref "X1") (pin "D-") (pinfunction "D-_D-") (pintype "bidirectional"))
    )
    (net (code "60") (name "Net-(IC1-OSC1)") (class "Default")
      (node (ref "C2") (pin "2") (pinfunction "2_2") (pintype "passive"))
      (node (ref "IC1") (pin "2") (pinfunction "OSC1_2") (pintype "bidirectional"))
      (node (ref "Q1") (pin "1") (pinfunction "1_1") (pintype "passive"))
    )
    (net (code "61") (name "Net-(IC1-OSC2)") (class "Default")
      (node (ref "C1") (pin "1") (pinfunction "1_1") (pintype "passive"))
      (node (ref "IC1") (pin "3") (pinfunction "OSC2_3") (pintype "bidirectional"))
      (node (ref "Q1") (pin "2") (pinfunction "2_2") (pintype "passive"))
    )
    (net (code "62") (name "Net-(IC1-RST)") (class "Default")
      (node (ref "IC1") (pin "4") (pinfunction "RST_4") (pintype "bidirectional"))
      (node (ref "R1") (pin "1") (pinfunction "1_1") (pintype "passive"))
      (node (ref "S1") (pin "3") (pinfunction "3_3") (pintype "passive"))
      (node (ref "S1") (pin "4") (pinfunction "4_4") (pintype "passive"))
    )
    (net (code "63") (name "Net-(IC1-RXLED)") (class "Default")
      (node (ref "IC1") (pin "6") (pinfunction "RXLED_6") (pintype "bidirectional"))
      (node (ref "R3") (pin "2") (pinfunction "2_2") (pintype "passive"))
    )
    (net (code "64") (name "Net-(IC1-TXLED)") (class "Default")
      (node (ref "IC1") (pin "5") (pinfunction "TXLED_5") (pintype "bidirectional"))
      (node (ref "R2") (pin "2") (pinfunction "2_2") (pintype "passive"))
    )
    (net (code "65") (name "Net-(IC1-VUSB)") (class "Default")
      (node (ref "C3") (pin "2") (pinfunction "2_2") (pintype "passive"))
      (node (ref "IC1") (pin "17") (pinfunction "VUSB_17") (pintype "bidirectional"))
    )
    (net (code "66") (name "Net-(IC2-AREF)") (class "Default")
      (node (ref "C23") (pin "1") (pinfunction "1_1") (pintype "passive"))
      (node (ref "IC2") (pin "32") (pinfunction "AREF_32") (pintype "passive"))
    )
    (net (code "67") (name "Net-(IC2-XTAL1)") (class "Default")
      (node (ref "C6") (pin "1") (pinfunction "1_1") (pintype "passive"))
      (node (ref "IC2") (pin "13") (pinfunction "XTAL1_13") (pintype "input"))
      (node (ref "Q2") (pin "2") (pinfunction "2_2") (pintype "passive"))
    )
    (net (code "68") (name "Net-(IC2-XTAL2)") (class "Default")
      (node (ref "C5") (pin "1") (pinfunction "1_1") (pintype "passive"))
      (node (ref "IC2") (pin "12") (pinfunction "XTAL2_12") (pintype "output"))
      (node (ref "Q2") (pin "1") (pinfunction "1_1") (pintype "passive"))
    )
    (net (code "69") (name "Net-(J1-5V-Pad21)") (class "Default")
      (node (ref "J1") (pin "21") (pinfunction "5V_21") (pintype "bidirectional"))
      (node (ref "J1") (pin "22") (pinfunction "5V_22") (pintype "bidirectional"))
      (node (ref "R16") (pin "2") (pinfunction "2_2") (pintype "passive"))
      (node (ref "SJ12") (pin "1") (pinfunction "1_1") (pintype "passive"))
    )
    (net (code "70") (name "Net-(J1-5V_STDBY)") (class "Default")
      (node (ref "J1") (pin "9") (pinfunction "5V_STDBY_9") (pintype "bidirectional"))
      (node (ref "R17") (pin "2") (pinfunction "2_2") (pintype "passive"))
      (node (ref "SJ11") (pin "1") (pinfunction "1_1") (pintype "passive"))
    )
    (net (code "71") (name "Net-(LED1-C)") (class "Default")
      (node (ref "LED1") (pin "K") (pinfunction "C_K") (pintype "passive"))
      (node (ref "R2") (pin "1") (pinfunction "1_1") (pintype "passive"))
    )
    (net (code "72") (name "Net-(LED2-C)") (class "Default")
      (node (ref "LED2") (pin "K") (pinfunction "C_K") (pintype "passive"))
      (node (ref "R3") (pin "1") (pinfunction "1_1") (pintype "passive"))
    )
    (net (code "73") (name "Net-(LED3-PadA)") (class "Default")
      (node (ref "LED3") (pin "A") (pinfunction "A_A") (pintype "passive"))
      (node (ref "R16") (pin "1") (pinfunction "1_1") (pintype "passive"))
    )
    (net (code "74") (name "Net-(LED4-PadA)") (class "Default")
      (node (ref "LED4") (pin "A") (pinfunction "A_A") (pintype "passive"))
      (node (ref "R17") (pin "1") (pinfunction "1_1") (pintype "passive"))
    )
    (net (code "75") (name "Net-(LED5-PadA)") (class "Default")
      (node (ref "LED5") (pin "A") (pinfunction "A_A") (pintype "passive"))
      (node (ref "R18") (pin "1") (pinfunction "1_1") (pintype "passive"))
    )
    (net (code "76") (name "Net-(LED6-PadA)") (class "Default")
      (node (ref "LED6") (pin "A") (pinfunction "A_A") (pintype "passive"))
      (node (ref "R19") (pin "1") (pinfunction "1_1") (pintype "passive"))
    )
    (net (code "77") (name "Net-(LED8-PadA)") (class "Default")
      (node (ref "LED8") (pin "A") (pinfunction "A_A") (pintype "passive"))
      (node (ref "R22") (pin "1") (pinfunction "1_1") (pintype "passive"))
    )
    (net (code "78") (name "Net-(Q3-PadG)") (class "Default")
      (node (ref "Q3") (pin "G") (pinfunction "G_G") (pintype "passive"))
      (node (ref "R13") (pin "2") (pinfunction "2_2") (pintype "passive"))
    )
    (net (code "79") (name "Net-(Q4-PadG)") (class "Default")
      (node (ref "Q4") (pin "G") (pinfunction "G_G") (pintype "passive"))
      (node (ref "R14") (pin "2") (pinfunction "2_2") (pintype "passive"))
    )
    (net (code "80") (name "Net-(Q6-PadG)") (class "Default")
      (node (ref "Q6") (pin "G") (pinfunction "G_G") (pintype "passive"))
      (node (ref "R21") (pin "2") (pinfunction "2_2") (pintype "passive"))
    )
    (net (code "81") (name "Net-(R5-Pad1)") (class "Default")
      (node (ref "R5") (pin "1") (pinfunction "1_1") (pintype "passive"))
      (node (ref "SJ1") (pin "1") (pinfunction "1_1") (pintype "passive"))
      (node (ref "SJ2") (pin "1") (pinfunction "1_1") (pintype "passive"))
      (node (ref "XPOLOLU") (pin "MS1") (pinfunction "MS1_MS1") (pintype "input"))
    )
    (net (code "82") (name "Net-(R6-Pad1)") (class "Default")
      (node (ref "R6") (pin "1") (pinfunction "1_1") (pintype "passive"))
      (node (ref "SJ3") (pin "1") (pinfunction "1_1") (pintype "passive"))
      (node (ref "SJ4") (pin "1") (pinfunction "1_1") (pintype "passive"))
      (node (ref "YPOLOLU") (pin "MS1") (pinfunction "MS1_MS1") (pintype "input"))
    )
    (net (code "83") (name "Net-(R7-Pad1)") (class "Default")
      (node (ref "R7") (pin "1") (pinfunction "1_1") (pintype "passive"))
      (node (ref "SJ5") (pin "1") (pinfunction "1_1") (pintype "passive"))
      (node (ref "SJ6") (pin "1") (pinfunction "1_1") (pintype "passive"))
      (node (ref "ZPOLOLU") (pin "MS1") (pinfunction "MS1_MS1") (pintype "input"))
    )
    (net (code "84") (name "Net-(SJ1-Pad2)") (class "Default")
      (node (ref "SJ1") (pin "2") (pinfunction "2_2") (pintype "passive"))
      (node (ref "XPOLOLU") (pin "MS2") (pinfunction "MS2_MS2") (pintype "input"))
    )
    (net (code "85") (name "Net-(SJ2-Pad2)") (class "Default")
      (node (ref "SJ2") (pin "2") (pinfunction "2_2") (pintype "passive"))
      (node (ref "XPOLOLU") (pin "MS3") (pinfunction "MS3_MS3") (pintype "input"))
    )
    (net (code "86") (name "Net-(SJ3-Pad2)") (class "Default")
      (node (ref "SJ3") (pin "2") (pinfunction "2_2") (pintype "passive"))
      (node (ref "YPOLOLU") (pin "MS2") (pinfunction "MS2_MS2") (pintype "input"))
    )
    (net (code "87") (name "Net-(SJ4-Pad2)") (class "Default")
      (node (ref "SJ4") (pin "2") (pinfunction "2_2") (pintype "passive"))
      (node (ref "YPOLOLU") (pin "MS3") (pinfunction "MS3_MS3") (pintype "input"))
    )
    (net (code "88") (name "Net-(SJ5-Pad2)") (class "Default")
      (node (ref "SJ5") (pin "2") (pinfunction "2_2") (pintype "passive"))
      (node (ref "ZPOLOLU") (pin "MS2") (pinfunction "MS2_MS2") (pintype "input"))
    )
    (net (code "89") (name "Net-(SJ6-Pad2)") (class "Default")
      (node (ref "SJ6") (pin "2") (pinfunction "2_2") (pintype "passive"))
      (node (ref "ZPOLOLU") (pin "MS3") (pinfunction "MS3_MS3") (pintype "input"))
    )
    (net (code "90") (name "Net-(XMOTORA-S)") (class "Default")
      (node (ref "XMOTOR") (pin "1") (pinfunction "S_1") (pintype "passive"))
      (node (ref "XPOLOLU") (pin "2B") (pinfunction "2B_2B") (pintype "output"))
    )
    (net (code "91") (name "Net-(XMOTORB-S)") (class "Default")
      (node (ref "XMOTOR") (pin "2") (pinfunction "S_2") (pintype "passive"))
      (node (ref "XPOLOLU") (pin "2A") (pinfunction "2A_2A") (pintype "output"))
    )
    (net (code "92") (name "Net-(XMOTORC-S)") (class "Default")
      (node (ref "XMOTOR") (pin "3") (pinfunction "S_3") (pintype "passive"))
      (node (ref "XPOLOLU") (pin "1A") (pinfunction "1A_1A") (pintype "output"))
    )
    (net (code "93") (name "Net-(XMOTORD-S)") (class "Default")
      (node (ref "XMOTOR") (pin "4") (pinfunction "S_4") (pintype "passive"))
      (node (ref "XPOLOLU") (pin "1B") (pinfunction "1B_1B") (pintype "output"))
    )
    (net (code "94") (name "Net-(XPOLOLU-SLEEP)") (class "Default")
      (node (ref "XPOLOLU") (pin "RST") (pinfunction "RST_RST") (pintype "input"))
      (node (ref "XPOLOLU") (pin "SLP") (pinfunction "SLEEP_SLP") (pintype "input"))
    )
    (net (code "95") (name "Net-(YMOTORA-S)") (class "Default")
      (node (ref "YMOTOR") (pin "1") (pinfunction "S_1") (pintype "passive"))
      (node (ref "YPOLOLU") (pin "2B") (pinfunction "2B_2B") (pintype "output"))
    )
    (net (code "96") (name "Net-(YMOTORB-S)") (class "Default")
      (node (ref "YMOTOR") (pin "2") (pinfunction "S_2") (pintype "passive"))
      (node (ref "YPOLOLU") (pin "2A") (pinfunction "2A_2A") (pintype "output"))
    )
    (net (code "97") (name "Net-(YMOTORC-S)") (class "Default")
      (node (ref "YMOTOR") (pin "3") (pinfunction "S_3") (pintype "passive"))
      (node (ref "YPOLOLU") (pin "1A") (pinfunction "1A_1A") (pintype "output"))
    )
    (net (code "98") (name "Net-(YMOTORD-S)") (class "Default")
      (node (ref "YMOTOR") (pin "4") (pinfunction "S_4") (pintype "passive"))
      (node (ref "YPOLOLU") (pin "1B") (pinfunction "1B_1B") (pintype "output"))
    )
    (net (code "99") (name "Net-(YPOLOLU-SLEEP)") (class "Default")
      (node (ref "YPOLOLU") (pin "RST") (pinfunction "RST_RST") (pintype "input"))
      (node (ref "YPOLOLU") (pin "SLP") (pinfunction "SLEEP_SLP") (pintype "input"))
    )
    (net (code "100") (name "Net-(ZMOTORA-S)") (class "Default")
      (node (ref "ZMOTOR") (pin "1") (pinfunction "S_1") (pintype "passive"))
      (node (ref "ZPOLOLU") (pin "2B") (pinfunction "2B_2B") (pintype "output"))
    )
    (net (code "101") (name "Net-(ZMOTORB-S)") (class "Default")
      (node (ref "ZMOTOR") (pin "2") (pinfunction "S_2") (pintype "passive"))
      (node (ref "ZPOLOLU") (pin "2A") (pinfunction "2A_2A") (pintype "output"))
    )
    (net (code "102") (name "Net-(ZMOTORC-S)") (class "Default")
      (node (ref "ZMOTOR") (pin "3") (pinfunction "S_3") (pintype "passive"))
      (node (ref "ZPOLOLU") (pin "1A") (pinfunction "1A_1A") (pintype "output"))
    )
    (net (code "103") (name "Net-(ZMOTORD-S)") (class "Default")
      (node (ref "ZMOTOR") (pin "4") (pinfunction "S_4") (pintype "passive"))
      (node (ref "ZPOLOLU") (pin "1B") (pinfunction "1B_1B") (pintype "output"))
    )
    (net (code "104") (name "Net-(ZPOLOLU-SLEEP)") (class "Default")
      (node (ref "ZPOLOLU") (pin "RST") (pinfunction "RST_RST") (pintype "input"))
      (node (ref "ZPOLOLU") (pin "SLP") (pinfunction "SLEEP_SLP") (pintype "input"))
    )
    (net (code "105") (name "VCC") (class "Default")
      (node (ref "C10") (pin "1") (pinfunction "1_1") (pintype "passive"))
      (node (ref "C11") (pin "1") (pinfunction "1_1") (pintype "passive"))
      (node (ref "C12") (pin "1") (pinfunction "1_1") (pintype "passive"))
      (node (ref "C18") (pin "1") (pinfunction "1_1") (pintype "passive"))
      (node (ref "C30") (pin "+") (pinfunction "+_+") (pintype "passive"))
      (node (ref "C4") (pin "1") (pinfunction "1_1") (pintype "passive"))
      (node (ref "C8") (pin "1") (pinfunction "1_1") (pintype "passive"))
      (node (ref "C9") (pin "1") (pinfunction "1_1") (pintype "passive"))
      (node (ref "EPOLOLU") (pin "VDD") (pinfunction "VDD_VDD") (pintype "power_in"))
      (node (ref "EPOLOLU2") (pin "VDD") (pinfunction "VDD_VDD") (pintype "power_in"))
      (node (ref "IC1") (pin "1") (pinfunction "VDD_1") (pintype "bidirectional"))
      (node (ref "IC2") (pin "10") (pinfunction "VCC_10") (pintype "power_in"))
      (node (ref "J2") (pin "2") (pinfunction "2_2") (pintype "passive"))
      (node (ref "L1") (pin "2") (pinfunction "2_2") (pintype "passive"))
      (node (ref "LED1") (pin "A") (pinfunction "A_A") (pintype "passive"))
      (node (ref "LED2") (pin "A") (pinfunction "A_A") (pintype "passive"))
      (node (ref "R1") (pin "2") (pinfunction "2_2") (pintype "passive"))
      (node (ref "R4") (pin "2") (pinfunction "2_2") (pintype "passive"))
      (node (ref "R5") (pin "2") (pinfunction "2_2") (pintype "passive"))
      (node (ref "R6") (pin "2") (pinfunction "2_2") (pintype "passive"))
      (node (ref "R7") (pin "2") (pinfunction "2_2") (pintype "passive"))
      (node (ref "R8") (pin "2") (pinfunction "2_2") (pintype "passive"))
      (node (ref "R9") (pin "2") (pinfunction "2_2") (pintype "passive"))
      (node (ref "SJ11") (pin "2") (pinfunction "2_2") (pintype "passive"))
      (node (ref "SJ12") (pin "2") (pinfunction "2_2") (pintype "passive"))
      (node (ref "X1") (pin "VBUS") (pinfunction "VBUS_VBUS") (pintype "bidirectional"))
      (node (ref "X5") (pin "1") (pinfunction "1_1") (pintype "passive"))
      (node (ref "X6") (pin "1") (pinfunction "1_1") (pintype "passive"))
      (node (ref "XENDSTOP") (pin "1") (pinfunction "S_1") (pintype "passive"))
      (node (ref "XPOLOLU") (pin "VDD") (pinfunction "VDD_VDD") (pintype "power_in"))
      (node (ref "YENDSTOP") (pin "1") (pinfunction "S_1") (pintype "passive"))
      (node (ref "YPOLOLU") (pin "VDD") (pinfunction "VDD_VDD") (pintype "power_in"))
      (node (ref "ZENDSTOP") (pin "1") (pinfunction "S_1") (pintype "passive"))
      (node (ref "ZPOLOLU") (pin "VDD") (pinfunction "VDD_VDD") (pintype "power_in"))
    )
    (net (code "106") (name "unconnected-(IC1-CTS-Pad13)") (class "Default")
      (node (ref "IC1") (pin "13") (pinfunction "CTS_13") (pintype "bidirectional"))
    )
    (net (code "107") (name "unconnected-(IC1-GPIO2-Pad14)") (class "Default")
      (node (ref "IC1") (pin "14") (pinfunction "GPIO2_14") (pintype "bidirectional"))
    )
    (net (code "108") (name "unconnected-(IC1-GPIO3-Pad9)") (class "Default")
      (node (ref "IC1") (pin "9") (pinfunction "GPIO3_9") (pintype "bidirectional"))
    )
    (net (code "109") (name "unconnected-(IC1-GPIO4-Pad8)") (class "Default")
      (node (ref "IC1") (pin "8") (pinfunction "GPIO4_8") (pintype "bidirectional"))
    )
    (net (code "110") (name "unconnected-(IC1-GPIO5-Pad7)") (class "Default")
      (node (ref "IC1") (pin "7") (pinfunction "GPIO5_7") (pintype "bidirectional"))
    )
    (net (code "111") (name "unconnected-(IC1-SSPND-Pad16)") (class "Default")
      (node (ref "IC1") (pin "16") (pinfunction "SSPND_16") (pintype "bidirectional"))
    )
    (net (code "112") (name "unconnected-(IC1-USBCFG-Pad15)") (class "Default")
      (node (ref "IC1") (pin "15") (pinfunction "USBCFG_15") (pintype "bidirectional"))
    )
    (net (code "113") (name "unconnected-(J1--12V-Pad14)") (class "Default")
      (node (ref "J1") (pin "14") (pinfunction "-12V_14") (pintype "bidirectional"))
    )
    (net (code "114") (name "unconnected-(J1-3.3V-Pad1)") (class "Default")
      (node (ref "J1") (pin "1") (pinfunction "3.3V_1") (pintype "bidirectional"))
    )
    (net (code "115") (name "unconnected-(J1-3.3V-Pad2)") (class "Default")
      (node (ref "J1") (pin "2") (pinfunction "3.3V_2") (pintype "bidirectional"))
    )
    (net (code "116") (name "unconnected-(J1-3.3V-Pad12)") (class "Default")
      (node (ref "J1") (pin "12") (pinfunction "3.3V_12") (pintype "bidirectional"))
    )
    (net (code "117") (name "unconnected-(J1-5V-Pad4)") (class "Default")
      (node (ref "J1") (pin "4") (pinfunction "5V_4") (pintype "bidirectional"))
    )
    (net (code "118") (name "unconnected-(J1-5V-Pad6)") (class "Default")
      (node (ref "J1") (pin "6") (pinfunction "5V_6") (pintype "bidirectional"))
    )
    (net (code "119") (name "unconnected-(J1-5V-Pad23)") (class "Default")
      (node (ref "J1") (pin "23") (pinfunction "5V_23") (pintype "bidirectional"))
    )
    (net (code "120") (name "unconnected-(J1-12V-Pad10)") (class "Default")
      (node (ref "J1") (pin "10") (pinfunction "12V_10") (pintype "bidirectional"))
    )
    (net (code "121") (name "unconnected-(J1-12V-Pad11)") (class "Default")
      (node (ref "J1") (pin "11") (pinfunction "12V_11") (pintype "bidirectional"))
    )
    (net (code "122") (name "unconnected-(J1-GND-Pad15)") (class "Default")
      (node (ref "J1") (pin "15") (pinfunction "GND_15") (pintype "bidirectional"))
    )
    (net (code "123") (name "unconnected-(J1-GND-Pad17)") (class "Default")
      (node (ref "J1") (pin "17") (pinfunction "GND_17") (pintype "bidirectional"))
    )
    (net (code "124") (name "unconnected-(J1-GND-Pad24)") (class "Default")
      (node (ref "J1") (pin "24") (pinfunction "GND_24") (pintype "bidirectional"))
    )
    (net (code "125") (name "unconnected-(J1-NC-Pad20)") (class "Default")
      (node (ref "J1") (pin "20") (pinfunction "NC_20") (pintype "bidirectional"))
    )
    (net (code "126") (name "unconnected-(J1-PWR_OK-Pad8)") (class "Default")
      (node (ref "J1") (pin "8") (pinfunction "PWR_OK_8") (pintype "bidirectional"))
    )
  )
)
